# encoder_final.net
KiCad netlist of a schematic drawn in EAGLE
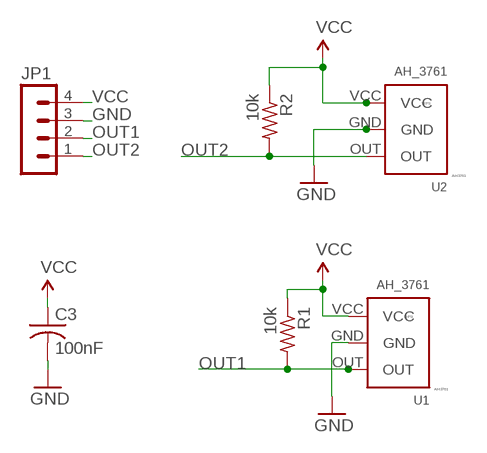
[diagram p0: schematic, sheet 1]

(export (version "E")
  (design (tool "Eeschema 10.0.6"))
  (components
    (comp (ref "C3")
      (value "100nF")
      (footprint "eagle-import:C2012")
      (libsource (lib "eagle-import") (part "C-USC2012"))
    )
    (comp (ref "JP1")
      (value "MA04-1")
      (footprint "eagle-import:MA04-1")
      (libsource (lib "eagle-import") (part "MA04-1"))
    )
    (comp (ref "R1")
      (value "10k")
      (footprint "eagle-import:R3216")
      (libsource (lib "eagle-import") (part "R-US_R3216"))
    )
    (comp (ref "R2")
      (value "10k")
      (footprint "eagle-import:R3216")
      (libsource (lib "eagle-import") (part "R-US_R3216"))
    )
    (comp (ref "U1")
      (value "AH_3761")
      (footprint "eagle-import:SIP3")
      (libsource (lib "eagle-import") (part "AH_3761"))
    )
    (comp (ref "U2")
      (value "AH_3761")
      (footprint "eagle-import:SIP3")
      (libsource (lib "eagle-import") (part "AH_3761"))
    )
  )
  (nets
    (net (code "1") (name "/OUT1") (class "Default")
      (node (ref "JP1") (pin "2") (pinfunction "2_2") (pintype "passive"))
      (node (ref "R1") (pin "2") (pinfunction "2_2") (pintype "passive"))
      (node (ref "U1") (pin "OUT") (pinfunction "OUT_OUT") (pintype "bidirectional"))
    )
    (net (code "2") (name "/OUT2") (class "Default")
      (node (ref "JP1") (pin "1") (pinfunction "1_1") (pintype "passive"))
      (node (ref "R2") (pin "2") (pinfunction "2_2") (pintype "passive"))
      (node (ref "U2") (pin "OUT") (pinfunction "OUT_OUT") (pintype "bidirectional"))
    )
    (net (code "3") (name "GND") (class "Default")
      (node (ref "C3") (pin "2") (pinfunction "2_2") (pintype "passive"))
      (node (ref "JP1") (pin "3") (pinfunction "3_3") (pintype "passive"))
      (node (ref "U1") (pin "GND") (pinfunction "GND_GND") (pintype "power_in"))
      (node (ref "U2") (pin "GND") (pinfunction "GND_GND") (pintype "power_in"))
    )
    (net (code "4") (name "VCC") (class "Default")
      (node (ref "C3") (pin "1") (pinfunction "1_1") (pintype "passive"))
      (node (ref "JP1") (pin "4") (pinfunction "4_4") (pintype "passive"))
      (node (ref "R1") (pin "1") (pinfunction "1_1") (pintype "passive"))
      (node (ref "R2") (pin "1") (pinfunction "1_1") (pintype "passive"))
      (node (ref "U1") (pin "VCC") (pinfunction "VCC_VCC") (pintype "power_in"))
      (node (ref "U2") (pin "VCC") (pinfunction "VCC_VCC") (pintype "power_in"))
    )
  )
)
